# Controlador_de_velocidad_v2.net
KiCad netlist of a schematic drawn in Altium Designer
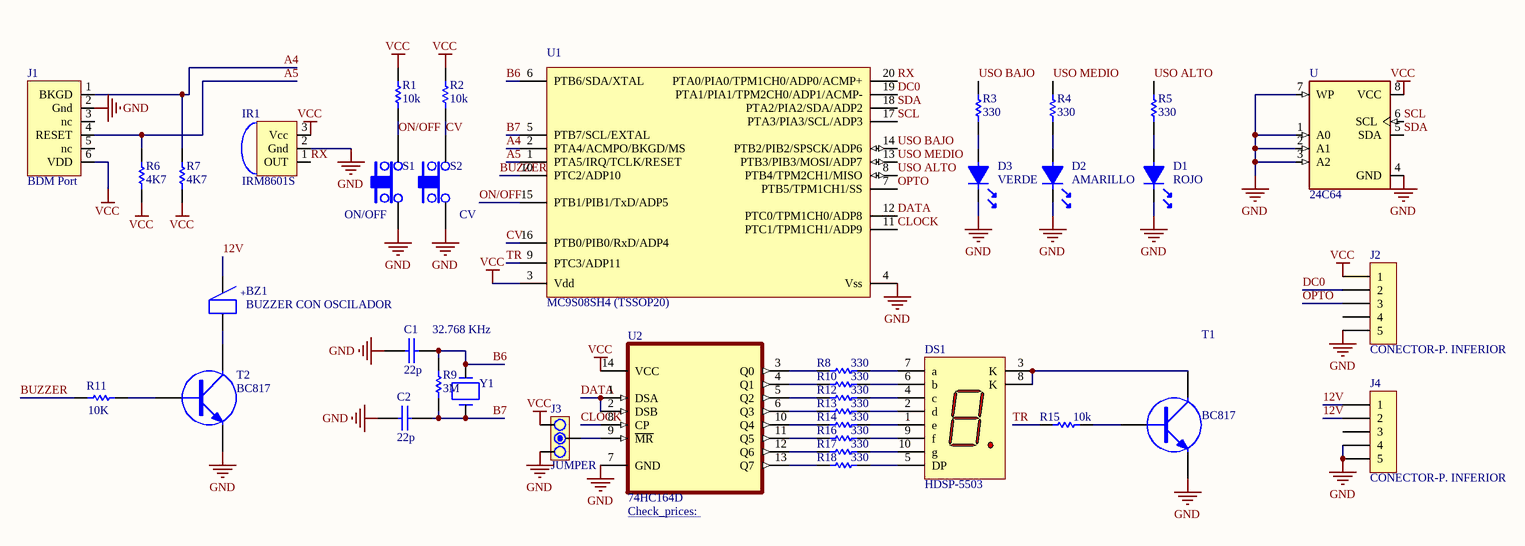
[diagram p0: Controlador de velocidad v2.SchDoc]

(export (version "E")
  (design (tool "Eeschema 10.0.6"))
  (components
    (comp (ref "BZ1")
      (value "BUZZER CON OSCILADOR")
      (footprint "BUZZER 12MM")
      (libsource (lib "LIBEBAL") (part "BUZZER"))
    )
    (comp (ref "C1") (value "22p") (footprint "0805") (libsource (lib "LIBPIOIX") (part "CAP")))
    (comp (ref "C2") (value "22p") (footprint "0805") (libsource (lib "LIBPIOIX") (part "CAP")))
    (comp (ref "D1") (value "ROJO") (footprint "LED5") (libsource (lib "LIBPIOIX") (part "LED")))
    (comp (ref "D2") (value "AMARILLO") (footprint "LED5") (libsource (lib "LIBPIOIX") (part "LED")))
    (comp (ref "D3") (value "VERDE") (footprint "LED5") (libsource (lib "LIBPIOIX") (part "LED")))
    (comp (ref "DS1")
      (value "HDSP-5503")
      (footprint "H-10")
      (description "14.22 mm Gray Surface HER 7-Segment Display: CC, RH DP")
      (fields (field (name "PUBLISHER") "Altium Limited"))
      (libsource (lib "Agilent LED Display 7-Segment, 1-Digit") (part "HDSP-5503"))
    )
    (comp (ref "IR1")
      (value "IRM8601S")
      (footprint "IRM8601S")
      (description "Sensor IR")
      (libsource (lib "*") (part "IRM8601S"))
    )
    (comp (ref "J1") (value "BDM Port") (footprint "JBDM") (libsource (lib "*") (part "JBDM")))
    (comp (ref "J2")
      (value "CONECTOR-P. INFERIOR")
      (footprint "SIP5")
      (libsource (lib "LIBEBAL") (part "CON5"))
    )
    (comp (ref "J3") (value "JUMPER") (footprint "JUMPER3") (libsource (lib "LIBPIOIX") (part "JUMPER3")))
    (comp (ref "J4")
      (value "CONECTOR-P. INFERIOR")
      (footprint "SIP5")
      (libsource (lib "LIBEBAL") (part "CON5"))
    )
    (comp (ref "R1") (value "10k") (footprint "0805") (libsource (lib "LIBPIOIX") (part "RES")))
    (comp (ref "R2") (value "10k") (footprint "0805") (libsource (lib "LIBPIOIX") (part "RES")))
    (comp (ref "R3") (value "330") (footprint "0805") (libsource (lib "LIBPIOIX") (part "RES")))
    (comp (ref "R4") (value "330") (footprint "0805") (libsource (lib "LIBPIOIX") (part "RES")))
    (comp (ref "R5") (value "330") (footprint "0805") (libsource (lib "LIBPIOIX") (part "RES")))
    (comp (ref "R6") (value "4K7") (footprint "0805") (libsource (lib "LIBPIOIX") (part "RES")))
    (comp (ref "R7") (value "4K7") (footprint "0805") (libsource (lib "LIBPIOIX") (part "RES")))
    (comp (ref "R8") (value "330") (footprint "0805") (libsource (lib "LIB PIO IX") (part "RES")))
    (comp (ref "R9") (value "3M") (footprint "0805") (libsource (lib "LIB PIO IX") (part "RES")))
    (comp (ref "R10") (value "330") (footprint "0805") (libsource (lib "LIB PIO IX") (part "RES")))
    (comp (ref "R11") (value "10K") (footprint "0805") (libsource (lib "LIBPIOIX") (part "RES")))
    (comp (ref "R12") (value "330") (footprint "0805") (libsource (lib "LIB PIO IX") (part "RES")))
    (comp (ref "R13") (value "330") (footprint "0805") (libsource (lib "LIB PIO IX") (part "RES")))
    (comp (ref "R14") (value "330") (footprint "0805") (libsource (lib "LIB PIO IX") (part "RES")))
    (comp (ref "R15") (value "10k") (footprint "0805") (libsource (lib "LIB PIO IX") (part "RES")))
    (comp (ref "R16") (value "330") (footprint "0805") (libsource (lib "LIB PIO IX") (part "RES")))
    (comp (ref "R17") (value "330") (footprint "0805") (libsource (lib "LIB PIO IX") (part "RES")))
    (comp (ref "R18") (value "330") (footprint "0805") (libsource (lib "LIB PIO IX") (part "RES")))
    (comp (ref "S1")
      (value "ON/OFF")
      (footprint "TACTSWITCH")
      (libsource (lib "LIBPIOIX") (part "TACT SWITCH"))
    )
    (comp (ref "S2") (value "CV") (footprint "TACTSWITCH") (libsource (lib "LIBPIOIX") (part "TACT SWITCH")))
    (comp (ref "T1") (value "BC817") (footprint "SOT23") (libsource (lib "LIBPIOIX") (part "TRANSISTOR NPN")))
    (comp (ref "T2") (value "BC817") (footprint "SOT23") (libsource (lib "LIBPIOIX") (part "TRANSISTOR NPN")))
    (comp (ref "U")
      (value "24C64")
      (footprint "SOIC127P600X175-8N")
      (description "EEPROM Memory IC 256Kb _32K x 8_ I²C 1MHz 550ns 8-SOIC")
      (fields
        (field (name "MP") "AT24C256C-SSHL-T")
        (field (name "DIGI-KEY_PART_NUMBER") "AT24C256C-SSHL-TCT-ND")
      )
      (libsource (lib "AT24C256C-SSHL-T") (part "AT24C256C-SSHL-T"))
    )
    (comp (ref "U1")
      (value "MC9S08SH4 (TSSOP20)")
      (footprint "TSSOP20")
      (libsource (lib "*") (part "MC9S08SH8_20"))
    )
    (comp (ref "U2")
      (value "74HC164D")
      (footprint "SOIC127P600X175-14N")
      (description "Shift Shift Register 1 Element 8 Bit 14-SO")
      (fields (field (name "MF") "Nexperia USA") (field (name "MP") "74HC164D,653"))
      (libsource (lib "74HC164D_653") (part "74HC164D,653"))
    )
    (comp (ref "Y1") (value "32.768 KHz") (footprint "X32768") (libsource (lib "*") (part "CRYSTAL")))
  )
  (nets
    (net (code "1") (name "/12V") (class "Default")
      (node (ref "BZ1") (pin "1") (pinfunction "1_1") (pintype "passive"))
      (node (ref "J4") (pin "1") (pinfunction "1_1") (pintype "passive"))
      (node (ref "J4") (pin "2") (pinfunction "2_2") (pintype "passive"))
    )
    (net (code "2") (name "/A4") (class "Default")
      (node (ref "J1") (pin "1") (pinfunction "BKGD_1") (pintype "passive"))
      (node (ref "R7") (pin "2") (pinfunction "2_2") (pintype "passive"))
      (node (ref "U1") (pin "2") (pinfunction "PTA4/ACMPO/BKGD/MS_2") (pintype "passive"))
    )
    (net (code "3") (name "/A5") (class "Default")
      (node (ref "J1") (pin "4") (pinfunction "RESET_4") (pintype "passive"))
      (node (ref "R6") (pin "2") (pinfunction "2_2") (pintype "passive"))
      (node (ref "U1") (pin "1") (pinfunction "PTA5/IRQ/TCLK/RESET_1") (pintype "passive"))
    )
    (net (code "4") (name "/B6") (class "Default")
      (node (ref "C1") (pin "1") (pinfunction "1_1") (pintype "passive"))
      (node (ref "R9") (pin "2") (pinfunction "2_2") (pintype "passive"))
      (node (ref "U1") (pin "6") (pinfunction "PTB6/SDA/XTAL_6") (pintype "passive"))
      (node (ref "Y1") (pin "2") (pinfunction "2_2") (pintype "passive"))
    )
    (net (code "5") (name "/B7") (class "Default")
      (node (ref "C2") (pin "1") (pinfunction "1_1") (pintype "passive"))
      (node (ref "R9") (pin "1") (pinfunction "1_1") (pintype "passive"))
      (node (ref "U1") (pin "5") (pinfunction "PTB7/SCL/EXTAL_5") (pintype "passive"))
      (node (ref "Y1") (pin "1") (pinfunction "1_1") (pintype "passive"))
    )
    (net (code "6") (name "/BUZZER") (class "Default")
      (node (ref "R11") (pin "1") (pinfunction "1_1") (pintype "passive"))
      (node (ref "U1") (pin "10") (pinfunction "PTC2/ADP10_10") (pintype "passive"))
    )
    (net (code "7") (name "/CLOCK") (class "Default")
      (node (ref "U1") (pin "11") (pinfunction "PTC1/TPM1CH1/ADP9_11") (pintype "passive"))
      (node (ref "U2") (pin "8") (pinfunction "CP_8") (pintype "input"))
    )
    (net (code "8") (name "/CV") (class "Default")
      (node (ref "R2") (pin "1") (pinfunction "1_1") (pintype "passive"))
      (node (ref "S2") (pin "2") (pinfunction "2_2") (pintype "passive"))
      (node (ref "U1") (pin "16") (pinfunction "PTB0/PIB0/RxD/ADP4_16") (pintype "passive"))
    )
    (net (code "9") (name "/DATA") (class "Default")
      (node (ref "U1") (pin "12") (pinfunction "PTC0/TPM1CH0/ADP8_12") (pintype "passive"))
      (node (ref "U2") (pin "1") (pinfunction "DSA_1") (pintype "input"))
      (node (ref "U2") (pin "2") (pinfunction "DSB_2") (pintype "input"))
    )
    (net (code "10") (name "/DC0") (class "Default")
      (node (ref "J2") (pin "2") (pinfunction "2_2") (pintype "passive"))
      (node (ref "U1") (pin "19") (pinfunction "PTA1/PIA1/TPM2CH0/ADP1/ACMP-_19") (pintype "passive"))
    )
    (net (code "11") (name "/ON{slash}OFF") (class "Default")
      (node (ref "R1") (pin "1") (pinfunction "1_1") (pintype "passive"))
      (node (ref "S1") (pin "2") (pinfunction "2_2") (pintype "passive"))
      (node (ref "U1") (pin "15") (pinfunction "PTB1/PIB1/TxD/ADP5_15") (pintype "passive"))
    )
    (net (code "12") (name "/OPTO") (class "Default")
      (node (ref "J2") (pin "3") (pinfunction "3_3") (pintype "passive"))
      (node (ref "U1") (pin "7") (pinfunction "PTB5/TPM1CH1/SS_7") (pintype "passive"))
    )
    (net (code "13") (name "/RX") (class "Default")
      (node (ref "IR1") (pin "1") (pinfunction "OUT_1") (pintype "passive"))
      (node (ref "U1") (pin "20") (pinfunction "PTA0/PIA0/TPM1CH0/ADP0/ACMP+_20") (pintype "passive"))
    )
    (net (code "14") (name "/SCL") (class "Default")
      (node (ref "U") (pin "6") (pinfunction "SCL_6") (pintype "input"))
      (node (ref "U1") (pin "17") (pinfunction "PTA3/PIA3/SCL/ADP3_17") (pintype "passive"))
    )
    (net (code "15") (name "/SDA") (class "Default")
      (node (ref "U") (pin "5") (pinfunction "SDA_5") (pintype "bidirectional"))
      (node (ref "U1") (pin "18") (pinfunction "PTA2/PIA2/SDA/ADP2_18") (pintype "passive"))
    )
    (net (code "16") (name "/TR") (class "Default")
      (node (ref "R15") (pin "1") (pinfunction "1_1") (pintype "passive"))
      (node (ref "U1") (pin "9") (pinfunction "PTC3/ADP11_9") (pintype "passive"))
    )
    (net (code "17") (name "/USO ALTO") (class "Default")
      (node (ref "R5") (pin "2") (pinfunction "2_2") (pintype "passive"))
      (node (ref "U1") (pin "8") (pinfunction "PTB4/TPM2CH1/MISO_8") (pintype "bidirectional"))
    )
    (net (code "18") (name "/USO BAJO") (class "Default")
      (node (ref "R3") (pin "2") (pinfunction "2_2") (pintype "passive"))
      (node (ref "U1") (pin "14") (pinfunction "PTB2/PIB2/SPSCK/ADP6_14") (pintype "bidirectional"))
    )
    (net (code "19") (name "/USO MEDIO") (class "Default")
      (node (ref "R4") (pin "2") (pinfunction "2_2") (pintype "passive"))
      (node (ref "U1") (pin "13") (pinfunction "PTB3/PIB3/MOSI/ADP7_13") (pintype "bidirectional"))
    )
    (net (code "20") (name "GND") (class "Default")
      (node (ref "C1") (pin "2") (pinfunction "2_2") (pintype "passive"))
      (node (ref "C2") (pin "2") (pinfunction "2_2") (pintype "passive"))
      (node (ref "D1") (pin "2") (pinfunction "2_2") (pintype "passive"))
      (node (ref "D2") (pin "2") (pinfunction "2_2") (pintype "passive"))
      (node (ref "D3") (pin "2") (pinfunction "2_2") (pintype "passive"))
      (node (ref "IR1") (pin "2") (pinfunction "Gnd_2") (pintype "passive"))
      (node (ref "J1") (pin "2") (pinfunction "Gnd_2") (pintype "passive"))
      (node (ref "J2") (pin "5") (pinfunction "5_5") (pintype "passive"))
      (node (ref "J3") (pin "1") (pinfunction "1_1") (pintype "passive"))
      (node (ref "J4") (pin "4") (pinfunction "4_4") (pintype "passive"))
      (node (ref "J4") (pin "5") (pinfunction "5_5") (pintype "passive"))
      (node (ref "S1") (pin "1") (pinfunction "1_1") (pintype "passive"))
      (node (ref "S2") (pin "1") (pinfunction "1_1") (pintype "passive"))
      (node (ref "T1") (pin "3") (pinfunction "E_3") (pintype "passive"))
      (node (ref "T2") (pin "3") (pinfunction "E_3") (pintype "passive"))
      (node (ref "U") (pin "1") (pinfunction "A0_1") (pintype "input"))
      (node (ref "U") (pin "2") (pinfunction "A1_2") (pintype "input"))
      (node (ref "U") (pin "3") (pinfunction "A2_3") (pintype "input"))
      (node (ref "U") (pin "4") (pinfunction "GND_4") (pintype "power_in"))
      (node (ref "U") (pin "7") (pinfunction "WP_7") (pintype "input"))
      (node (ref "U1") (pin "4") (pinfunction "Vss_4") (pintype "passive"))
      (node (ref "U2") (pin "7") (pinfunction "GND_7") (pintype "passive"))
    )
    (net (code "21") (name "Net-(D1-Pad1)") (class "Default")
      (node (ref "D1") (pin "1") (pinfunction "1_1") (pintype "passive"))
      (node (ref "R5") (pin "1") (pinfunction "1_1") (pintype "passive"))
    )
    (net (code "22") (name "Net-(D2-Pad1)") (class "Default")
      (node (ref "D2") (pin "1") (pinfunction "1_1") (pintype "passive"))
      (node (ref "R4") (pin "1") (pinfunction "1_1") (pintype "passive"))
    )
    (net (code "23") (name "Net-(D3-Pad1)") (class "Default")
      (node (ref "D3") (pin "1") (pinfunction "1_1") (pintype "passive"))
      (node (ref "R3") (pin "1") (pinfunction "1_1") (pintype "passive"))
    )
    (net (code "24") (name "Net-(DS1-DP)") (class "Default")
      (node (ref "DS1") (pin "5") (pinfunction "DP_5") (pintype "passive"))
      (node (ref "R18") (pin "2") (pinfunction "2_2") (pintype "passive"))
    )
    (net (code "25") (name "Net-(DS1-a)") (class "Default")
      (node (ref "DS1") (pin "7") (pinfunction "a_7") (pintype "passive"))
      (node (ref "R8") (pin "2") (pinfunction "2_2") (pintype "passive"))
    )
    (net (code "26") (name "Net-(DS1-b)") (class "Default")
      (node (ref "DS1") (pin "6") (pinfunction "b_6") (pintype "passive"))
      (node (ref "R10") (pin "2") (pinfunction "2_2") (pintype "passive"))
    )
    (net (code "27") (name "Net-(DS1-c)") (class "Default")
      (node (ref "DS1") (pin "4") (pinfunction "c_4") (pintype "passive"))
      (node (ref "R12") (pin "2") (pinfunction "2_2") (pintype "passive"))
    )
    (net (code "28") (name "Net-(DS1-d)") (class "Default")
      (node (ref "DS1") (pin "2") (pinfunction "d_2") (pintype "passive"))
      (node (ref "R13") (pin "2") (pinfunction "2_2") (pintype "passive"))
    )
    (net (code "29") (name "Net-(DS1-e)") (class "Default")
      (node (ref "DS1") (pin "1") (pinfunction "e_1") (pintype "passive"))
      (node (ref "R14") (pin "2") (pinfunction "2_2") (pintype "passive"))
    )
    (net (code "30") (name "Net-(DS1-f)") (class "Default")
      (node (ref "DS1") (pin "9") (pinfunction "f_9") (pintype "passive"))
      (node (ref "R16") (pin "2") (pinfunction "2_2") (pintype "passive"))
    )
    (net (code "31") (name "Net-(DS1-g)") (class "Default")
      (node (ref "DS1") (pin "10") (pinfunction "g_10") (pintype "passive"))
      (node (ref "R17") (pin "2") (pinfunction "2_2") (pintype "passive"))
    )
    (net (code "32") (name "Net-(T1-B)") (class "Default")
      (node (ref "R15") (pin "2") (pinfunction "2_2") (pintype "passive"))
      (node (ref "T1") (pin "1") (pinfunction "B_1") (pintype "passive"))
    )
    (net (code "33") (name "Net-(T1-C)") (class "Default")
      (node (ref "DS1") (pin "3") (pinfunction "K_3") (pintype "passive"))
      (node (ref "DS1") (pin "8") (pinfunction "K_8") (pintype "passive"))
      (node (ref "T1") (pin "2") (pinfunction "C_2") (pintype "passive"))
    )
    (net (code "34") (name "Net-(T2-B)") (class "Default")
      (node (ref "R11") (pin "2") (pinfunction "2_2") (pintype "passive"))
      (node (ref "T2") (pin "1") (pinfunction "B_1") (pintype "passive"))
    )
    (net (code "35") (name "Net-(T2-C)") (class "Default")
      (node (ref "BZ1") (pin "2") (pinfunction "2_2") (pintype "passive"))
      (node (ref "T2") (pin "2") (pinfunction "C_2") (pintype "passive"))
    )
    (net (code "36") (name "Net-(U2-Q0)") (class "Default")
      (node (ref "R8") (pin "1") (pinfunction "1_1") (pintype "passive"))
      (node (ref "U2") (pin "3") (pinfunction "Q0_3") (pintype "output"))
    )
    (net (code "37") (name "Net-(U2-Q1)") (class "Default")
      (node (ref "R10") (pin "1") (pinfunction "1_1") (pintype "passive"))
      (node (ref "U2") (pin "4") (pinfunction "Q1_4") (pintype "output"))
    )
    (net (code "38") (name "Net-(U2-Q2)") (class "Default")
      (node (ref "R12") (pin "1") (pinfunction "1_1") (pintype "passive"))
      (node (ref "U2") (pin "5") (pinfunction "Q2_5") (pintype "output"))
    )
    (net (code "39") (name "Net-(U2-Q3)") (class "Default")
      (node (ref "R13") (pin "1") (pinfunction "1_1") (pintype "passive"))
      (node (ref "U2") (pin "6") (pinfunction "Q3_6") (pintype "output"))
    )
    (net (code "40") (name "Net-(U2-Q4)") (class "Default")
      (node (ref "R14") (pin "1") (pinfunction "1_1") (pintype "passive"))
      (node (ref "U2") (pin "10") (pinfunction "Q4_10") (pintype "output"))
    )
    (net (code "41") (name "Net-(U2-Q5)") (class "Default")
      (node (ref "R16") (pin "1") (pinfunction "1_1") (pintype "passive"))
      (node (ref "U2") (pin "11") (pinfunction "Q5_11") (pintype "output"))
    )
    (net (code "42") (name "Net-(U2-Q6)") (class "Default")
      (node (ref "R17") (pin "1") (pinfunction "1_1") (pintype "passive"))
      (node (ref "U2") (pin "12") (pinfunction "Q6_12") (pintype "output"))
    )
    (net (code "43") (name "Net-(U2-Q7)") (class "Default")
      (node (ref "R18") (pin "1") (pinfunction "1_1") (pintype "passive"))
      (node (ref "U2") (pin "13") (pinfunction "Q7_13") (pintype "output"))
    )
    (net (code "44") (name "Net-(U2-~{MR})") (class "Default")
      (node (ref "J3") (pin "2") (pinfunction "2_2") (pintype "passive"))
      (node (ref "U2") (pin "9") (pinfunction "~{MR}_9") (pintype "input"))
    )
    (net (code "45") (name "VCC") (class "Default")
      (node (ref "IR1") (pin "3") (pinfunction "Vcc_3") (pintype "passive"))
      (node (ref "J1") (pin "6") (pinfunction "VDD_6") (pintype "passive"))
      (node (ref "J2") (pin "1") (pinfunction "1_1") (pintype "passive"))
      (node (ref "J3") (pin "3") (pinfunction "3_3") (pintype "passive"))
      (node (ref "R1") (pin "2") (pinfunction "2_2") (pintype "passive"))
      (node (ref "R2") (pin "2") (pinfunction "2_2") (pintype "passive"))
      (node (ref "R6") (pin "1") (pinfunction "1_1") (pintype "passive"))
      (node (ref "R7") (pin "1") (pinfunction "1_1") (pintype "passive"))
      (node (ref "U") (pin "8") (pinfunction "VCC_8") (pintype "power_in"))
      (node (ref "U1") (pin "3") (pinfunction "Vdd_3") (pintype "passive"))
      (node (ref "U2") (pin "14") (pinfunction "VCC_14") (pintype "power_in"))
    )
    (net (code "46") (name "unconnected-(J1-nc-Pad3)") (class "Default")
      (node (ref "J1") (pin "3") (pinfunction "nc_3") (pintype "passive"))
    )
    (net (code "47") (name "unconnected-(J1-nc-Pad5)") (class "Default")
      (node (ref "J1") (pin "5") (pinfunction "nc_5") (pintype "passive"))
    )
    (net (code "48") (name "unconnected-(J2-Pad4)") (class "Default")
      (node (ref "J2") (pin "4") (pinfunction "4_4") (pintype "passive"))
    )
    (net (code "49") (name "unconnected-(J4-Pad3)") (class "Default")
      (node (ref "J4") (pin "3") (pinfunction "3_3") (pintype "passive"))
    )
  )
)
